# CM_DDR3.net
KiCad netlist of a schematic drawn in Altium Designer
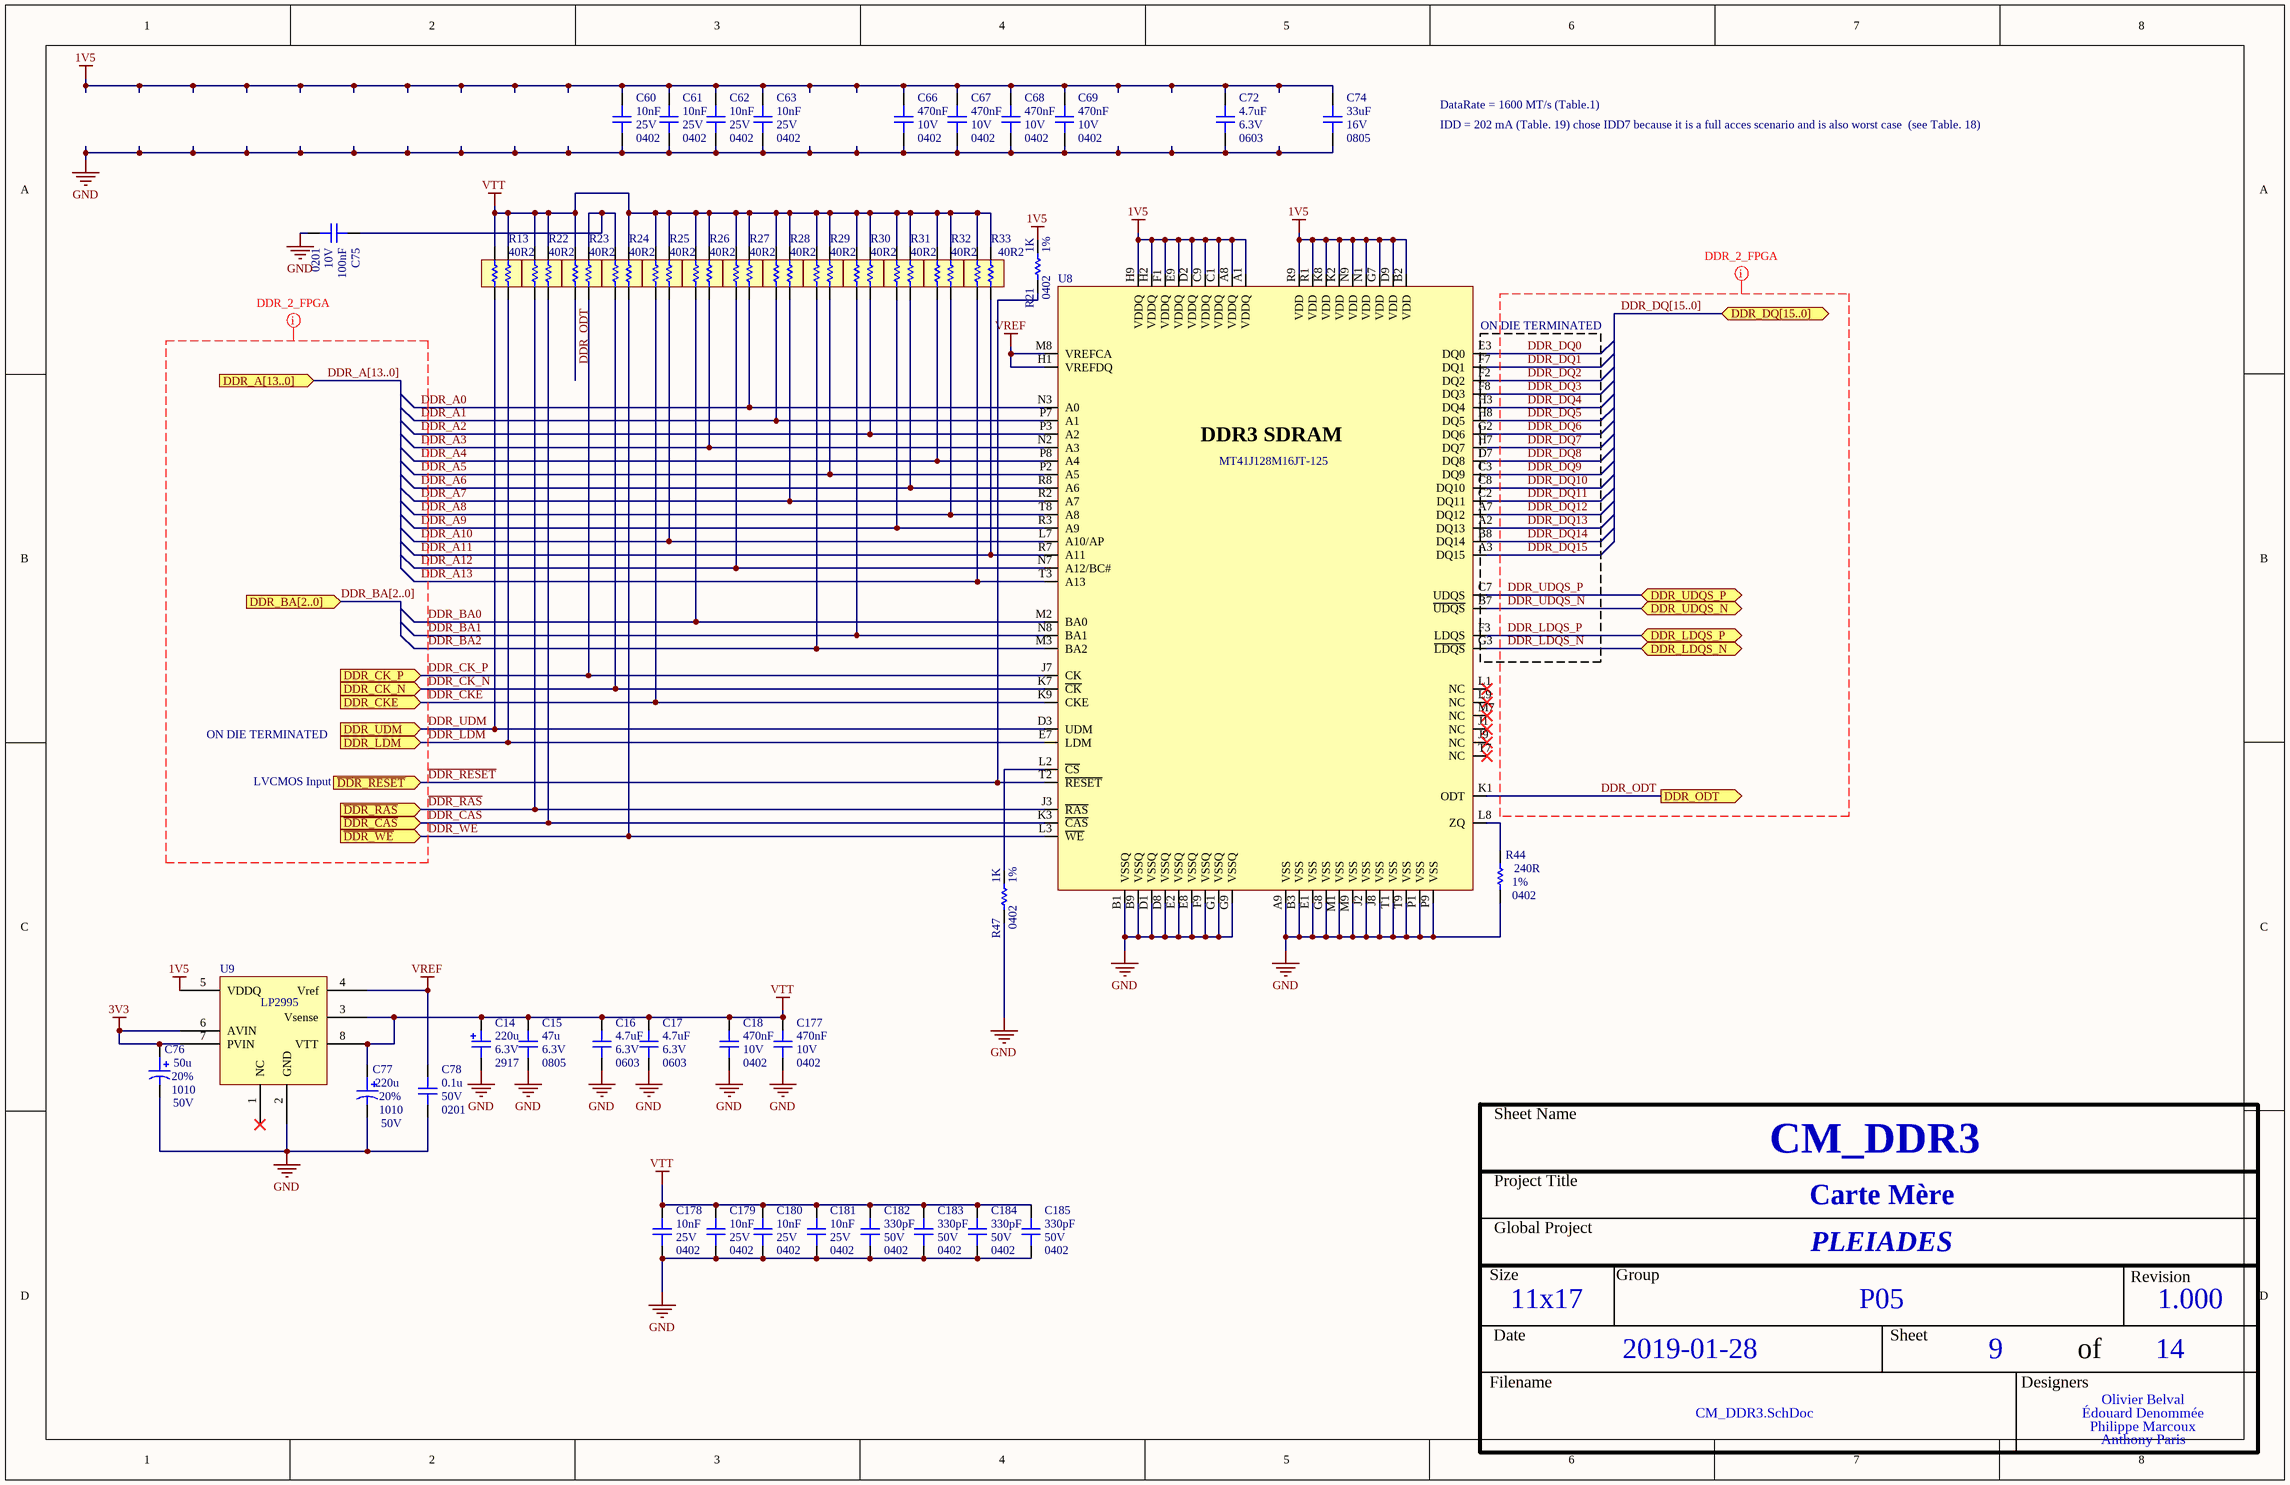
[diagram p0: CM_DDR3.SchDoc]

(export (version "E")
  (design (tool "Eeschema 10.0.6"))
  (components
    (comp (ref "C14")
      (value "220u")
      (footprint "CAP_TAN_2917(D)")
      (description "CAP - TANTALUM - 2917")
      (fields
        (field (name "VOLTAGE") "6.3V")
        (field (name "PACKAGE") "2917")
        (field (name "Comment") "CAP - TANTALUM - CASE D")
        (field (name "CREATEDBY") "Jonathan Bouchard")
      )
      (libsource (lib "S7CAS_Lib2019_REV1_00") (part "CAP_TANT_2917(D)"))
    )
    (comp (ref "C15")
      (value "47u")
      (footprint "CAP_0805")
      (description "CAP - 0805")
      (fields
        (field (name "VOLTAGE") "6.3V")
        (field (name "PACKAGE") "0805")
        (field (name "CREATEDBY") "Jonathan Bouchard")
      )
      (libsource (lib "S7CAS_Lib2019_REV1_00") (part "CAP - 0805"))
    )
    (comp (ref "C16")
      (value "4.7uF")
      (footprint "CAP_0603")
      (description "CAP - 0603")
      (fields
        (field (name "VOLTAGE") "6.3V")
        (field (name "PACKAGE") "0603")
        (field (name "CREATEDBY") "Jonathan Bouchard")
      )
      (libsource (lib "S7CAS_Lib2019_REV1_00") (part "CAP - 0603"))
    )
    (comp (ref "C17")
      (value "4.7uF")
      (footprint "CAP_0603")
      (description "CAP - 0603")
      (fields
        (field (name "VOLTAGE") "6.3V")
        (field (name "PACKAGE") "0603")
        (field (name "CREATEDBY") "Jonathan Bouchard")
      )
      (libsource (lib "S7CAS_Lib2019_REV1_00") (part "CAP - 0603"))
    )
    (comp (ref "C18")
      (value "470nF")
      (footprint "CAP_0402")
      (description "CAP - 0402")
      (fields
        (field (name "VOLTAGE") "10V")
        (field (name "PACKAGE") "0402")
        (field (name "CREATEDBY") "Jonathan Bouchard")
      )
      (libsource (lib "S7CAS_Lib2019_REV1_00") (part "CAP - 0402"))
    )
    (comp (ref "C60")
      (value "10nF")
      (footprint "CAP_0402")
      (description "CAP - 0402")
      (fields
        (field (name "VOLTAGE") "25V")
        (field (name "PACKAGE") "0402")
        (field (name "CREATEDBY") "Jonathan Bouchard")
      )
      (libsource (lib "S7CAS_Lib2019_REV1_00") (part "CAP - 0402"))
    )
    (comp (ref "C61")
      (value "10nF")
      (footprint "CAP_0402")
      (description "CAP - 0402")
      (fields
        (field (name "VOLTAGE") "25V")
        (field (name "PACKAGE") "0402")
        (field (name "CREATEDBY") "Jonathan Bouchard")
      )
      (libsource (lib "S7CAS_Lib2019_REV1_00") (part "CAP - 0402"))
    )
    (comp (ref "C62")
      (value "10nF")
      (footprint "CAP_0402")
      (description "CAP - 0402")
      (fields
        (field (name "VOLTAGE") "25V")
        (field (name "PACKAGE") "0402")
        (field (name "CREATEDBY") "Jonathan Bouchard")
      )
      (libsource (lib "S7CAS_Lib2019_REV1_00") (part "CAP - 0402"))
    )
    (comp (ref "C63")
      (value "10nF")
      (footprint "CAP_0402")
      (description "CAP - 0402")
      (fields
        (field (name "VOLTAGE") "25V")
        (field (name "PACKAGE") "0402")
        (field (name "CREATEDBY") "Jonathan Bouchard")
      )
      (libsource (lib "S7CAS_Lib2019_REV1_00") (part "CAP - 0402"))
    )
    (comp (ref "C66")
      (value "470nF")
      (footprint "CAP_0402")
      (description "CAP - 0402")
      (fields
        (field (name "VOLTAGE") "10V")
        (field (name "PACKAGE") "0402")
        (field (name "CREATEDBY") "Jonathan Bouchard")
      )
      (libsource (lib "S7CAS_Lib2019_REV1_00") (part "CAP - 0402"))
    )
    (comp (ref "C67")
      (value "470nF")
      (footprint "CAP_0402")
      (description "CAP - 0402")
      (fields
        (field (name "VOLTAGE") "10V")
        (field (name "PACKAGE") "0402")
        (field (name "CREATEDBY") "Jonathan Bouchard")
      )
      (libsource (lib "S7CAS_Lib2019_REV1_00") (part "CAP - 0402"))
    )
    (comp (ref "C68")
      (value "470nF")
      (footprint "CAP_0402")
      (description "CAP - 0402")
      (fields
        (field (name "VOLTAGE") "10V")
        (field (name "PACKAGE") "0402")
        (field (name "CREATEDBY") "Jonathan Bouchard")
      )
      (libsource (lib "S7CAS_Lib2019_REV1_00") (part "CAP - 0402"))
    )
    (comp (ref "C69")
      (value "470nF")
      (footprint "CAP_0402")
      (description "CAP - 0402")
      (fields
        (field (name "VOLTAGE") "10V")
        (field (name "PACKAGE") "0402")
        (field (name "CREATEDBY") "Jonathan Bouchard")
      )
      (libsource (lib "S7CAS_Lib2019_REV1_00") (part "CAP - 0402"))
    )
    (comp (ref "C72")
      (value "4.7uF")
      (footprint "CAP_0603")
      (description "CAP - 0603")
      (fields
        (field (name "VOLTAGE") "6.3V")
        (field (name "PACKAGE") "0603")
        (field (name "CREATEDBY") "Jonathan Bouchard")
      )
      (libsource (lib "S7CAS_Lib2019_REV1_00") (part "CAP - 0603"))
    )
    (comp (ref "C74")
      (value "33uF")
      (footprint "CAP_0805")
      (description "CAP - 0805")
      (fields
        (field (name "VOLTAGE") "16V")
        (field (name "PACKAGE") "0805")
        (field (name "CREATEDBY") "Jonathan Bouchard")
      )
      (libsource (lib "S7CAS_Lib2019_REV1_00") (part "CAP - 0805"))
    )
    (comp (ref "C75")
      (value "100nF")
      (footprint "CAP_0201")
      (description "CAP - 0201")
      (fields
        (field (name "VOLTAGE") "10V")
        (field (name "PACKAGE") "0201")
        (field (name "CREATEDBY") "Jonathan Bouchard")
      )
      (libsource (lib "S7CAS_Lib2019_REV1_00") (part "CAP - 0201"))
    )
    (comp (ref "C76")
      (value "50u")
      (footprint "CAP_ALU_1010_vishay")
      (description "CAP - ALU 100uF 20% 50V - 1010")
      (fields
        (field (name "MFG") "Vishay Dale")
        (field (name "MFG PART NUMBER") "MAL215099101E3")
        (field (name "VOLTAGE") "50V")
        (field (name "PACKAGE") "1010")
        (field (name "PRECISION") "20%")
        (field (name "CREATEDBY") "Jonathan Bouchard")
      )
      (libsource (lib "S7CAS_Lib2019_REV1_00") (part "CAP_ALU_MAL215099101E3"))
    )
    (comp (ref "C77")
      (value "220u")
      (footprint "CAP_ALU_1010_vishay")
      (description "CAP - ALU 100uF 20% 50V - 1010")
      (fields
        (field (name "MFG") "Vishay Dale")
        (field (name "MFG PART NUMBER") "MAL215099101E3")
        (field (name "VOLTAGE") "50V")
        (field (name "PACKAGE") "1010")
        (field (name "PRECISION") "20%")
        (field (name "CREATEDBY") "Jonathan Bouchard")
      )
      (libsource (lib "S7CAS_Lib2019_REV1_00") (part "CAP_ALU_MAL215099101E3"))
    )
    (comp (ref "C78")
      (value "0.1u")
      (footprint "CAP_0201")
      (description "CAP - 0201")
      (fields
        (field (name "VOLTAGE") "50V")
        (field (name "PACKAGE") "0201")
        (field (name "CREATEDBY") "Jonathan Bouchard")
      )
      (libsource (lib "S7CAS_Lib2019_REV1_00") (part "CAP - 0201"))
    )
    (comp (ref "C177")
      (value "470nF")
      (footprint "CAP_0402")
      (description "CAP - 0402")
      (fields
        (field (name "VOLTAGE") "10V")
        (field (name "PACKAGE") "0402")
        (field (name "CREATEDBY") "Jonathan Bouchard")
      )
      (libsource (lib "S7CAS_Lib2019_REV1_00") (part "CAP - 0402"))
    )
    (comp (ref "C178")
      (value "10nF")
      (footprint "CAP_0402")
      (description "CAP - 0402")
      (fields
        (field (name "VOLTAGE") "25V")
        (field (name "PACKAGE") "0402")
        (field (name "CREATEDBY") "Jonathan Bouchard")
      )
      (libsource (lib "S7CAS_Lib2019_REV1_00") (part "CAP - 0402"))
    )
    (comp (ref "C179")
      (value "10nF")
      (footprint "CAP_0402")
      (description "CAP - 0402")
      (fields
        (field (name "VOLTAGE") "25V")
        (field (name "PACKAGE") "0402")
        (field (name "CREATEDBY") "Jonathan Bouchard")
      )
      (libsource (lib "S7CAS_Lib2019_REV1_00") (part "CAP - 0402"))
    )
    (comp (ref "C180")
      (value "10nF")
      (footprint "CAP_0402")
      (description "CAP - 0402")
      (fields
        (field (name "VOLTAGE") "25V")
        (field (name "PACKAGE") "0402")
        (field (name "CREATEDBY") "Jonathan Bouchard")
      )
      (libsource (lib "S7CAS_Lib2019_REV1_00") (part "CAP - 0402"))
    )
    (comp (ref "C181")
      (value "10nF")
      (footprint "CAP_0402")
      (description "CAP - 0402")
      (fields
        (field (name "VOLTAGE") "25V")
        (field (name "PACKAGE") "0402")
        (field (name "CREATEDBY") "Jonathan Bouchard")
      )
      (libsource (lib "S7CAS_Lib2019_REV1_00") (part "CAP - 0402"))
    )
    (comp (ref "C182")
      (value "330pF")
      (footprint "CAP_0402")
      (description "CAP - 0402")
      (fields
        (field (name "VOLTAGE") "50V")
        (field (name "PACKAGE") "0402")
        (field (name "CREATEDBY") "Jonathan Bouchard")
      )
      (libsource (lib "S7CAS_Lib2019_REV1_00") (part "CAP - 0402"))
    )
    (comp (ref "C183")
      (value "330pF")
      (footprint "CAP_0402")
      (description "CAP - 0402")
      (fields
        (field (name "VOLTAGE") "50V")
        (field (name "PACKAGE") "0402")
        (field (name "CREATEDBY") "Jonathan Bouchard")
      )
      (libsource (lib "S7CAS_Lib2019_REV1_00") (part "CAP - 0402"))
    )
    (comp (ref "C184")
      (value "330pF")
      (footprint "CAP_0402")
      (description "CAP - 0402")
      (fields
        (field (name "VOLTAGE") "50V")
        (field (name "PACKAGE") "0402")
        (field (name "CREATEDBY") "Jonathan Bouchard")
      )
      (libsource (lib "S7CAS_Lib2019_REV1_00") (part "CAP - 0402"))
    )
    (comp (ref "C185")
      (value "330pF")
      (footprint "CAP_0402")
      (description "CAP - 0402")
      (fields
        (field (name "VOLTAGE") "50V")
        (field (name "PACKAGE") "0402")
        (field (name "CREATEDBY") "Jonathan Bouchard")
      )
      (libsource (lib "S7CAS_Lib2019_REV1_00") (part "CAP - 0402"))
    )
    (comp (ref "R13")
      (value "40R2")
      (footprint "CAT16-J2")
      (fields (field (name "Comment") "Double resistor"))
      (libsource (lib "Double res") (part "Double resistor"))
    )
    (comp (ref "R21")
      (value "1K")
      (footprint "RES_0402")
      (description "RES - 0402")
      (fields
        (field (name "VOLTAGE") "50V")
        (field (name "POWER") "1/16W")
        (field (name "PACKAGE") "0402")
        (field (name "PRECISION") "1%")
        (field (name "CREATEDBY") "Jonathan Bouchard")
      )
      (libsource (lib "S7CAS_Lib2019_REV1_00") (part "RES - 0402"))
    )
    (comp (ref "R22")
      (value "40R2")
      (footprint "CAT16-J2")
      (fields (field (name "Comment") "Double resistor"))
      (libsource (lib "Double res") (part "Double resistor"))
    )
    (comp (ref "R23")
      (value "40R2")
      (footprint "CAT16-J2")
      (fields (field (name "Comment") "Double resistor"))
      (libsource (lib "Double res") (part "Double resistor"))
    )
    (comp (ref "R24")
      (value "40R2")
      (footprint "CAT16-J2")
      (fields (field (name "Comment") "Double resistor"))
      (libsource (lib "Double res") (part "Double resistor"))
    )
    (comp (ref "R25")
      (value "40R2")
      (footprint "CAT16-J2")
      (fields (field (name "Comment") "Double resistor"))
      (libsource (lib "Double res") (part "Double resistor"))
    )
    (comp (ref "R26")
      (value "40R2")
      (footprint "CAT16-J2")
      (fields (field (name "Comment") "Double resistor"))
      (libsource (lib "Double res") (part "Double resistor"))
    )
    (comp (ref "R27")
      (value "40R2")
      (footprint "CAT16-J2")
      (fields (field (name "Comment") "Double resistor"))
      (libsource (lib "Double res") (part "Double resistor"))
    )
    (comp (ref "R28")
      (value "40R2")
      (footprint "CAT16-J2")
      (fields (field (name "Comment") "Double resistor"))
      (libsource (lib "Double res") (part "Double resistor"))
    )
    (comp (ref "R29")
      (value "40R2")
      (footprint "CAT16-J2")
      (fields (field (name "Comment") "Double resistor"))
      (libsource (lib "Double res") (part "Double resistor"))
    )
    (comp (ref "R30")
      (value "40R2")
      (footprint "CAT16-J2")
      (fields (field (name "Comment") "Double resistor"))
      (libsource (lib "Double res") (part "Double resistor"))
    )
    (comp (ref "R31")
      (value "40R2")
      (footprint "CAT16-J2")
      (fields (field (name "Comment") "Double resistor"))
      (libsource (lib "Double res") (part "Double resistor"))
    )
    (comp (ref "R32")
      (value "40R2")
      (footprint "CAT16-J2")
      (fields (field (name "Comment") "Double resistor"))
      (libsource (lib "Double res") (part "Double resistor"))
    )
    (comp (ref "R33")
      (value "40R2")
      (footprint "CAT16-J2")
      (fields (field (name "Comment") "Double resistor"))
      (libsource (lib "Double res") (part "Double resistor"))
    )
    (comp (ref "R44")
      (value "240R")
      (footprint "RES_0402")
      (description "RES - 0402")
      (fields
        (field (name "VOLTAGE") "50V")
        (field (name "POWER") "1/16W")
        (field (name "PACKAGE") "0402")
        (field (name "PRECISION") "1%")
        (field (name "CREATEDBY") "Jonathan Bouchard")
      )
      (libsource (lib "S7CAS_Lib2019_REV1_00") (part "RES - 0402"))
    )
    (comp (ref "R47")
      (value "1K")
      (footprint "RES_0402")
      (description "RES - 0402")
      (fields
        (field (name "VOLTAGE") "50V")
        (field (name "POWER") "1/16W")
        (field (name "PACKAGE") "0402")
        (field (name "PRECISION") "1%")
        (field (name "CREATEDBY") "Jonathan Bouchard")
      )
      (libsource (lib "S7CAS_Lib2019_REV1_00") (part "RES - 0402"))
    )
    (comp (ref "U8")
      (value "MT41J128M16JT-125")
      (footprint "MEM_DDR3_MT41J128M16JT-125")
      (description "MEM - DDR3 SDRAM 2GBIT 800MHZ - TFBGA-96")
      (fields
        (field (name "VOLTAGE") "1.425 V ~ 1.575 V")
        (field (name "MFG") "Micrel")
        (field (name "CREATEDBY") "Jonathan Bouchard")
      )
      (libsource (lib "S7CAS_Lib2019_REV1_00") (part "MEM_DDR3_MT41J128M16JT-125{colon}K TR"))
    )
    (comp (ref "U9") (value "LP2995") (footprint "SOP8") (libsource (lib "LP2995") (part "LP2995")))
  )
  (nets
    (net (code "1") (name "/DDR_A0") (class "Default")
      (node (ref "R27") (pin "2") (pinfunction "2_2") (pintype "passive"))
      (node (ref "U8") (pin "N3") (pinfunction "A0_N3") (pintype "passive"))
    )
    (net (code "2") (name "/DDR_A1") (class "Default")
      (node (ref "R28") (pin "1") (pinfunction "1_1") (pintype "passive"))
      (node (ref "U8") (pin "P7") (pinfunction "A1_P7") (pintype "passive"))
    )
    (net (code "3") (name "/DDR_A2") (class "Default")
      (node (ref "R30") (pin "2") (pinfunction "2_2") (pintype "passive"))
      (node (ref "U8") (pin "P3") (pinfunction "A2_P3") (pintype "passive"))
    )
    (net (code "4") (name "/DDR_A3") (class "Default")
      (node (ref "R26") (pin "2") (pinfunction "2_2") (pintype "passive"))
      (node (ref "U8") (pin "N2") (pinfunction "A3_N2") (pintype "passive"))
    )
    (net (code "5") (name "/DDR_A4") (class "Default")
      (node (ref "R32") (pin "1") (pinfunction "1_1") (pintype "passive"))
      (node (ref "U8") (pin "P8") (pinfunction "A4_P8") (pintype "passive"))
    )
    (net (code "6") (name "/DDR_A5") (class "Default")
      (node (ref "R29") (pin "2") (pinfunction "2_2") (pintype "passive"))
      (node (ref "U8") (pin "P2") (pinfunction "A5_P2") (pintype "passive"))
    )
    (net (code "7") (name "/DDR_A6") (class "Default")
      (node (ref "R31") (pin "2") (pinfunction "2_2") (pintype "passive"))
      (node (ref "U8") (pin "R8") (pinfunction "A6_R8") (pintype "passive"))
    )
    (net (code "8") (name "/DDR_A7") (class "Default")
      (node (ref "R28") (pin "2") (pinfunction "2_2") (pintype "passive"))
      (node (ref "U8") (pin "R2") (pinfunction "A7_R2") (pintype "passive"))
    )
    (net (code "9") (name "/DDR_A8") (class "Default")
      (node (ref "R32") (pin "2") (pinfunction "2_2") (pintype "passive"))
      (node (ref "U8") (pin "T8") (pinfunction "A8_T8") (pintype "passive"))
    )
    (net (code "10") (name "/DDR_A9") (class "Default")
      (node (ref "R31") (pin "1") (pinfunction "1_1") (pintype "passive"))
      (node (ref "U8") (pin "R3") (pinfunction "A9_R3") (pintype "passive"))
    )
    (net (code "11") (name "/DDR_A10") (class "Default")
      (node (ref "R25") (pin "2") (pinfunction "2_2") (pintype "passive"))
      (node (ref "U8") (pin "L7") (pinfunction "A10/AP_L7") (pintype "passive"))
    )
    (net (code "12") (name "/DDR_A11") (class "Default")
      (node (ref "R33") (pin "2") (pinfunction "2_2") (pintype "passive"))
      (node (ref "U8") (pin "R7") (pinfunction "A11_R7") (pintype "passive"))
    )
    (net (code "13") (name "/DDR_A12") (class "Default")
      (node (ref "R27") (pin "1") (pinfunction "1_1") (pintype "passive"))
      (node (ref "U8") (pin "N7") (pinfunction "A12/BC#_N7") (pintype "passive"))
    )
    (net (code "14") (name "/DDR_A13") (class "Default")
      (node (ref "R33") (pin "1") (pinfunction "1_1") (pintype "passive"))
      (node (ref "U8") (pin "T3") (pinfunction "A13_T3") (pintype "passive"))
    )
    (net (code "16") (name "/DDR_BA0") (class "Default")
      (node (ref "R26") (pin "1") (pinfunction "1_1") (pintype "passive"))
      (node (ref "U8") (pin "M2") (pinfunction "BA0_M2") (pintype "passive"))
    )
    (net (code "17") (name "/DDR_BA1") (class "Default")
      (node (ref "R30") (pin "1") (pinfunction "1_1") (pintype "passive"))
      (node (ref "U8") (pin "N8") (pinfunction "BA1_N8") (pintype "passive"))
    )
    (net (code "18") (name "/DDR_BA2") (class "Default")
      (node (ref "R29") (pin "1") (pinfunction "1_1") (pintype "passive"))
      (node (ref "U8") (pin "M3") (pinfunction "BA2_M3") (pintype "passive"))
    )
    (net (code "20") (name "/DDR_CAS") (class "Default")
      (node (ref "R22") (pin "2") (pinfunction "2_2") (pintype "passive"))
      (node (ref "U8") (pin "K3") (pinfunction "CAS_K3") (pintype "passive"))
    )
    (net (code "21") (name "/DDR_CKE") (class "Default")
      (node (ref "R25") (pin "1") (pinfunction "1_1") (pintype "passive"))
      (node (ref "U8") (pin "K9") (pinfunction "CKE_K9") (pintype "passive"))
    )
    (net (code "22") (name "/DDR_CK_N") (class "Default")
      (node (ref "R24") (pin "1") (pinfunction "1_1") (pintype "passive"))
      (node (ref "U8") (pin "K7") (pinfunction "CK_K7") (pintype "passive"))
    )
    (net (code "23") (name "/DDR_CK_P") (class "Default")
      (node (ref "R23") (pin "2") (pinfunction "2_2") (pintype "passive"))
      (node (ref "U8") (pin "J7") (pinfunction "CK_J7") (pintype "passive"))
    )
    (net (code "24") (name "/DDR_DQ0") (class "Default")
      (node (ref "U8") (pin "E3") (pinfunction "DQ0_E3") (pintype "passive"))
    )
    (net (code "25") (name "/DDR_DQ1") (class "Default")
      (node (ref "U8") (pin "F7") (pinfunction "DQ1_F7") (pintype "passive"))
    )
    (net (code "26") (name "/DDR_DQ2") (class "Default")
      (node (ref "U8") (pin "F2") (pinfunction "DQ2_F2") (pintype "passive"))
    )
    (net (code "27") (name "/DDR_DQ3") (class "Default")
      (node (ref "U8") (pin "F8") (pinfunction "DQ3_F8") (pintype "passive"))
    )
    (net (code "28") (name "/DDR_DQ4") (class "Default")
      (node (ref "U8") (pin "H3") (pinfunction "DQ4_H3") (pintype "passive"))
    )
    (net (code "29") (name "/DDR_DQ5") (class "Default")
      (node (ref "U8") (pin "H8") (pinfunction "DQ5_H8") (pintype "passive"))
    )
    (net (code "30") (name "/DDR_DQ6") (class "Default")
      (node (ref "U8") (pin "G2") (pinfunction "DQ6_G2") (pintype "passive"))
    )
    (net (code "31") (name "/DDR_DQ7") (class "Default")
      (node (ref "U8") (pin "H7") (pinfunction "DQ7_H7") (pintype "passive"))
    )
    (net (code "32") (name "/DDR_DQ8") (class "Default")
      (node (ref "U8") (pin "D7") (pinfunction "DQ8_D7") (pintype "passive"))
    )
    (net (code "33") (name "/DDR_DQ9") (class "Default")
      (node (ref "U8") (pin "C3") (pinfunction "DQ9_C3") (pintype "passive"))
    )
    (net (code "34") (name "/DDR_DQ10") (class "Default")
      (node (ref "U8") (pin "C8") (pinfunction "DQ10_C8") (pintype "passive"))
    )
    (net (code "35") (name "/DDR_DQ11") (class "Default")
      (node (ref "U8") (pin "C2") (pinfunction "DQ11_C2") (pintype "passive"))
    )
    (net (code "36") (name "/DDR_DQ12") (class "Default")
      (node (ref "U8") (pin "A7") (pinfunction "DQ12_A7") (pintype "passive"))
    )
    (net (code "37") (name "/DDR_DQ13") (class "Default")
      (node (ref "U8") (pin "A2") (pinfunction "DQ13_A2") (pintype "passive"))
    )
    (net (code "38") (name "/DDR_DQ14") (class "Default")
      (node (ref "U8") (pin "B8") (pinfunction "DQ14_B8") (pintype "passive"))
    )
    (net (code "39") (name "/DDR_DQ15") (class "Default")
      (node (ref "U8") (pin "A3") (pinfunction "DQ15_A3") (pintype "passive"))
    )
    (net (code "41") (name "/DDR_LDM") (class "Default")
      (node (ref "R13") (pin "2") (pinfunction "2_2") (pintype "passive"))
      (node (ref "U8") (pin "E7") (pinfunction "LDM_E7") (pintype "passive"))
    )
    (net (code "42") (name "/DDR_LDQS_N") (class "Default")
      (node (ref "U8") (pin "G3") (pinfunction "LDQS_G3") (pintype "passive"))
    )
    (net (code "43") (name "/DDR_LDQS_P") (class "Default")
      (node (ref "U8") (pin "F3") (pinfunction "LDQS_F3") (pintype "passive"))
    )
    (net (code "44") (name "/DDR_ODT") (class "Default")
      (node (ref "R23") (pin "1") (pinfunction "1_1") (pintype "passive"))
      (node (ref "U8") (pin "K1") (pinfunction "ODT_K1") (pintype "passive"))
    )
    (net (code "45") (name "/DDR_RAS") (class "Default")
      (node (ref "R22") (pin "1") (pinfunction "1_1") (pintype "passive"))
      (node (ref "U8") (pin "J3") (pinfunction "RAS_J3") (pintype "passive"))
    )
    (net (code "46") (name "/DDR_RESET") (class "Default")
      (node (ref "R21") (pin "1") (pinfunction "1_1") (pintype "passive"))
      (node (ref "U8") (pin "T2") (pinfunction "RESET_T2") (pintype "passive"))
    )
    (net (code "47") (name "/DDR_UDM") (class "Default")
      (node (ref "R13") (pin "1") (pinfunction "1_1") (pintype "passive"))
      (node (ref "U8") (pin "D3") (pinfunction "UDM_D3") (pintype "passive"))
    )
    (net (code "48") (name "/DDR_UDQS_N") (class "Default")
      (node (ref "U8") (pin "B7") (pinfunction "UDQS_B7") (pintype "passive"))
    )
    (net (code "49") (name "/DDR_UDQS_P") (class "Default")
      (node (ref "U8") (pin "C7") (pinfunction "UDQS_C7") (pintype "passive"))
    )
    (net (code "50") (name "/DDR_WE") (class "Default")
      (node (ref "R24") (pin "2") (pinfunction "2_2") (pintype "passive"))
      (node (ref "U8") (pin "L3") (pinfunction "WE_L3") (pintype "passive"))
    )
    (net (code "51") (name "1V5") (class "Default")
      (node (ref "C60") (pin "2") (pinfunction "2_2") (pintype "passive"))
      (node (ref "C61") (pin "2") (pinfunction "2_2") (pintype "passive"))
      (node (ref "C62") (pin "2") (pinfunction "2_2") (pintype "passive"))
      (node (ref "C63") (pin "2") (pinfunction "2_2") (pintype "passive"))
      (node (ref "C66") (pin "2") (pinfunction "2_2") (pintype "passive"))
      (node (ref "C67") (pin "2") (pinfunction "2_2") (pintype "passive"))
      (node (ref "C68") (pin "2") (pinfunction "2_2") (pintype "passive"))
      (node (ref "C69") (pin "2") (pinfunction "2_2") (pintype "passive"))
      (node (ref "C72") (pin "2") (pinfunction "2_2") (pintype "passive"))
      (node (ref "C74") (pin "2") (pinfunction "2_2") (pintype "passive"))
      (node (ref "R21") (pin "2") (pinfunction "2_2") (pintype "passive"))
      (node (ref "U8") (pin "A1") (pinfunction "VDDQ_A1") (pintype "power_in"))
      (node (ref "U8") (pin "A8") (pinfunction "VDDQ_A8") (pintype "power_in"))
      (node (ref "U8") (pin "B2") (pinfunction "VDD_B2") (pintype "power_in"))
      (node (ref "U8") (pin "C1") (pinfunction "VDDQ_C1") (pintype "power_in"))
      (node (ref "U8") (pin "C9") (pinfunction "VDDQ_C9") (pintype "power_in"))
      (node (ref "U8") (pin "D2") (pinfunction "VDDQ_D2") (pintype "power_in"))
      (node (ref "U8") (pin "D9") (pinfunction "VDD_D9") (pintype "power_in"))
      (node (ref "U8") (pin "E9") (pinfunction "VDDQ_E9") (pintype "power_in"))
      (node (ref "U8") (pin "F1") (pinfunction "VDDQ_F1") (pintype "power_in"))
      (node (ref "U8") (pin "G7") (pinfunction "VDD_G7") (pintype "power_in"))
      (node (ref "U8") (pin "H2") (pinfunction "VDDQ_H2") (pintype "power_in"))
      (node (ref "U8") (pin "H9") (pinfunction "VDDQ_H9") (pintype "power_in"))
      (node (ref "U8") (pin "K2") (pinfunction "VDD_K2") (pintype "power_in"))
      (node (ref "U8") (pin "K8") (pinfunction "VDD_K8") (pintype "power_in"))
      (node (ref "U8") (pin "N1") (pinfunction "VDD_N1") (pintype "power_in"))
      (node (ref "U8") (pin "N9") (pinfunction "VDD_N9") (pintype "power_in"))
      (node (ref "U8") (pin "R1") (pinfunction "VDD_R1") (pintype "power_in"))
      (node (ref "U8") (pin "R9") (pinfunction "VDD_R9") (pintype "power_in"))
      (node (ref "U9") (pin "5") (pinfunction "VDDQ_5") (pintype "passive"))
    )
    (net (code "52") (name "3V3") (class "Default")
      (node (ref "C76") (pin "1") (pinfunction "1_1") (pintype "passive"))
      (node (ref "U9") (pin "6") (pinfunction "AVIN_6") (pintype "passive"))
      (node (ref "U9") (pin "7") (pinfunction "PVIN_7") (pintype "passive"))
    )
    (net (code "53") (name "GND") (class "Default")
      (node (ref "C14") (pin "1") (pinfunction "1_1") (pintype "passive"))
      (node (ref "C15") (pin "1") (pinfunction "1_1") (pintype "passive"))
      (node (ref "C16") (pin "1") (pinfunction "1_1") (pintype "passive"))
      (node (ref "C17") (pin "1") (pinfunction "1_1") (pintype "passive"))
      (node (ref "C177") (pin "1") (pinfunction "1_1") (pintype "passive"))
      (node (ref "C178") (pin "1") (pinfunction "1_1") (pintype "passive"))
      (node (ref "C179") (pin "1") (pinfunction "1_1") (pintype "passive"))
      (node (ref "C18") (pin "1") (pinfunction "1_1") (pintype "passive"))
      (node (ref "C180") (pin "1") (pinfunction "1_1") (pintype "passive"))
      (node (ref "C181") (pin "1") (pinfunction "1_1") (pintype "passive"))
      (node (ref "C182") (pin "1") (pinfunction "1_1") (pintype "passive"))
      (node (ref "C183") (pin "1") (pinfunction "1_1") (pintype "passive"))
      (node (ref "C184") (pin "1") (pinfunction "1_1") (pintype "passive"))
      (node (ref "C185") (pin "1") (pinfunction "1_1") (pintype "passive"))
      (node (ref "C60") (pin "1") (pinfunction "1_1") (pintype "passive"))
      (node (ref "C61") (pin "1") (pinfunction "1_1") (pintype "passive"))
      (node (ref "C62") (pin "1") (pinfunction "1_1") (pintype "passive"))
      (node (ref "C63") (pin "1") (pinfunction "1_1") (pintype "passive"))
      (node (ref "C66") (pin "1") (pinfunction "1_1") (pintype "passive"))
      (node (ref "C67") (pin "1") (pinfunction "1_1") (pintype "passive"))
      (node (ref "C68") (pin "1") (pinfunction "1_1") (pintype "passive"))
      (node (ref "C69") (pin "1") (pinfunction "1_1") (pintype "passive"))
      (node (ref "C72") (pin "1") (pinfunction "1_1") (pintype "passive"))
      (node (ref "C74") (pin "1") (pinfunction "1_1") (pintype "passive"))
      (node (ref "C75") (pin "1") (pinfunction "1_1") (pintype "passive"))
      (node (ref "C76") (pin "2") (pinfunction "2_2") (pintype "passive"))
      (node (ref "C77") (pin "2") (pinfunction "2_2") (pintype "passive"))
      (node (ref "C78") (pin "1") (pinfunction "1_1") (pintype "passive"))
      (node (ref "R44") (pin "1") (pinfunction "1_1") (pintype "passive"))
      (node (ref "R47") (pin "1") (pinfunction "1_1") (pintype "passive"))
      (node (ref "U8") (pin "A9") (pinfunction "VSS_A9") (pintype "passive"))
      (node (ref "U8") (pin "B1") (pinfunction "VSSQ_B1") (pintype "passive"))
      (node (ref "U8") (pin "B3") (pinfunction "VSS_B3") (pintype "passive"))
      (node (ref "U8") (pin "B9") (pinfunction "VSSQ_B9") (pintype "passive"))
      (node (ref "U8") (pin "D1") (pinfunction "VSSQ_D1") (pintype "passive"))
      (node (ref "U8") (pin "D8") (pinfunction "VSSQ_D8") (pintype "passive"))
      (node (ref "U8") (pin "E1") (pinfunction "VSS_E1") (pintype "passive"))
      (node (ref "U8") (pin "E2") (pinfunction "VSSQ_E2") (pintype "passive"))
      (node (ref "U8") (pin "E8") (pinfunction "VSSQ_E8") (pintype "passive"))
      (node (ref "U8") (pin "F9") (pinfunction "VSSQ_F9") (pintype "passive"))
      (node (ref "U8") (pin "G1") (pinfunction "VSSQ_G1") (pintype "passive"))
      (node (ref "U8") (pin "G8") (pinfunction "VSS_G8") (pintype "passive"))
      (node (ref "U8") (pin "G9") (pinfunction "VSSQ_G9") (pintype "passive"))
      (node (ref "U8") (pin "J2") (pinfunction "VSS_J2") (pintype "passive"))
      (node (ref "U8") (pin "J8") (pinfunction "VSS_J8") (pintype "passive"))
      (node (ref "U8") (pin "M1") (pinfunction "VSS_M1") (pintype "passive"))
      (node (ref "U8") (pin "M9") (pinfunction "VSS_M9") (pintype "passive"))
      (node (ref "U8") (pin "P1") (pinfunction "VSS_P1") (pintype "passive"))
      (node (ref "U8") (pin "P9") (pinfunction "VSS_P9") (pintype "passive"))
      (node (ref "U8") (pin "T1") (pinfunction "VSS_T1") (pintype "passive"))
      (node (ref "U8") (pin "T9") (pinfunction "VSS_T9") (pintype "passive"))
      (node (ref "U9") (pin "2") (pinfunction "GND_2") (pintype "passive"))
    )
    (net (code "54") (name "Net-(C75-Pad2)") (class "Default")
      (node (ref "C75") (pin "2") (pinfunction "2_2") (pintype "passive"))
      (node (ref "R23") (pin "3") (pinfunction "3_3") (pintype "passive"))
      (node (ref "R24") (pin "4") (pinfunction "4_4") (pintype "passive"))
    )
    (net (code "55") (name "Net-(U8-CS)") (class "Default")
      (node (ref "R47") (pin "2") (pinfunction "2_2") (pintype "passive"))
      (node (ref "U8") (pin "L2") (pinfunction "CS_L2") (pintype "passive"))
    )
    (net (code "56") (name "Net-(U8-ZQ)") (class "Default")
      (node (ref "R44") (pin "2") (pinfunction "2_2") (pintype "passive"))
      (node (ref "U8") (pin "L8") (pinfunction "ZQ_L8") (pintype "passive"))
    )
    (net (code "57") (name "VREF") (class "Default")
      (node (ref "C78") (pin "2") (pinfunction "2_2") (pintype "passive"))
      (node (ref "U8") (pin "H1") (pinfunction "VREFDQ_H1") (pintype "passive"))
      (node (ref "U8") (pin "M8") (pinfunction "VREFCA_M8") (pintype "passive"))
      (node (ref "U9") (pin "4") (pinfunction "Vref_4") (pintype "passive"))
    )
    (net (code "58") (name "VTT") (class "Default")
      (node (ref "C14") (pin "2") (pinfunction "2_2") (pintype "passive"))
      (node (ref "C15") (pin "2") (pinfunction "2_2") (pintype "passive"))
      (node (ref "C16") (pin "2") (pinfunction "2_2") (pintype "passive"))
      (node (ref "C17") (pin "2") (pinfunction "2_2") (pintype "passive"))
      (node (ref "C177") (pin "2") (pinfunction "2_2") (pintype "passive"))
      (node (ref "C178") (pin "2") (pinfunction "2_2") (pintype "passive"))
      (node (ref "C179") (pin "2") (pinfunction "2_2") (pintype "passive"))
      (node (ref "C18") (pin "2") (pinfunction "2_2") (pintype "passive"))
      (node (ref "C180") (pin "2") (pinfunction "2_2") (pintype "passive"))
      (node (ref "C181") (pin "2") (pinfunction "2_2") (pintype "passive"))
      (node (ref "C182") (pin "2") (pinfunction "2_2") (pintype "passive"))
      (node (ref "C183") (pin "2") (pinfunction "2_2") (pintype "passive"))
      (node (ref "C184") (pin "2") (pinfunction "2_2") (pintype "passive"))
      (node (ref "C185") (pin "2") (pinfunction "2_2") (pintype "passive"))
      (node (ref "C77") (pin "1") (pinfunction "1_1") (pintype "passive"))
      (node (ref "R13") (pin "3") (pinfunction "3_3") (pintype "passive"))
      (node (ref "R13") (pin "4") (pinfunction "4_4") (pintype "passive"))
      (node (ref "R22") (pin "3") (pinfunction "3_3") (pintype "passive"))
      (node (ref "R22") (pin "4") (pinfunction "4_4") (pintype "passive"))
      (node (ref "R23") (pin "4") (pinfunction "4_4") (pintype "passive"))
      (node (ref "R24") (pin "3") (pinfunction "3_3") (pintype "passive"))
      (node (ref "R25") (pin "3") (pinfunction "3_3") (pintype "passive"))
      (node (ref "R25") (pin "4") (pinfunction "4_4") (pintype "passive"))
      (node (ref "R26") (pin "3") (pinfunction "3_3") (pintype "passive"))
      (node (ref "R26") (pin "4") (pinfunction "4_4") (pintype "passive"))
      (node (ref "R27") (pin "3") (pinfunction "3_3") (pintype "passive"))
      (node (ref "R27") (pin "4") (pinfunction "4_4") (pintype "passive"))
      (node (ref "R28") (pin "3") (pinfunction "3_3") (pintype "passive"))
      (node (ref "R28") (pin "4") (pinfunction "4_4") (pintype "passive"))
      (node (ref "R29") (pin "3") (pinfunction "3_3") (pintype "passive"))
      (node (ref "R29") (pin "4") (pinfunction "4_4") (pintype "passive"))
      (node (ref "R30") (pin "3") (pinfunction "3_3") (pintype "passive"))
      (node (ref "R30") (pin "4") (pinfunction "4_4") (pintype "passive"))
      (node (ref "R31") (pin "3") (pinfunction "3_3") (pintype "passive"))
      (node (ref "R31") (pin "4") (pinfunction "4_4") (pintype "passive"))
      (node (ref "R32") (pin "3") (pinfunction "3_3") (pintype "passive"))
      (node (ref "R32") (pin "4") (pinfunction "4_4") (pintype "passive"))
      (node (ref "R33") (pin "3") (pinfunction "3_3") (pintype "passive"))
      (node (ref "R33") (pin "4") (pinfunction "4_4") (pintype "passive"))
      (node (ref "U9") (pin "3") (pinfunction "Vsense_3") (pintype "passive"))
      (node (ref "U9") (pin "8") (pinfunction "VTT_8") (pintype "passive"))
    )
    (net (code "59") (name "unconnected-(U8-NC-PadJ1)") (class "Default")
      (node (ref "U8") (pin "J1") (pinfunction "NC_J1") (pintype "passive+no_connect"))
    )
    (net (code "60") (name "unconnected-(U8-NC-PadJ9)") (class "Default")
      (node (ref "U8") (pin "J9") (pinfunction "NC_J9") (pintype "passive+no_connect"))
    )
    (net (code "61") (name "unconnected-(U8-NC-PadL1)") (class "Default")
      (node (ref "U8") (pin "L1") (pinfunction "NC_L1") (pintype "passive+no_connect"))
    )
    (net (code "62") (name "unconnected-(U8-NC-PadL9)") (class "Default")
      (node (ref "U8") (pin "L9") (pinfunction "NC_L9") (pintype "passive+no_connect"))
    )
    (net (code "63") (name "unconnected-(U8-NC-PadM7)") (class "Default")
      (node (ref "U8") (pin "M7") (pinfunction "NC_M7") (pintype "passive+no_connect"))
    )
    (net (code "64") (name "unconnected-(U8-NC-PadT7)") (class "Default")
      (node (ref "U8") (pin "T7") (pinfunction "NC_T7") (pintype "passive+no_connect"))
    )
    (net (code "65") (name "unconnected-(U9-NC-Pad1)") (class "Default")
      (node (ref "U9") (pin "1") (pinfunction "NC_1") (pintype "passive+no_connect"))
    )
  )
)
